# BreakoutBoard.net
KiCad netlist of a schematic drawn in EAGLE
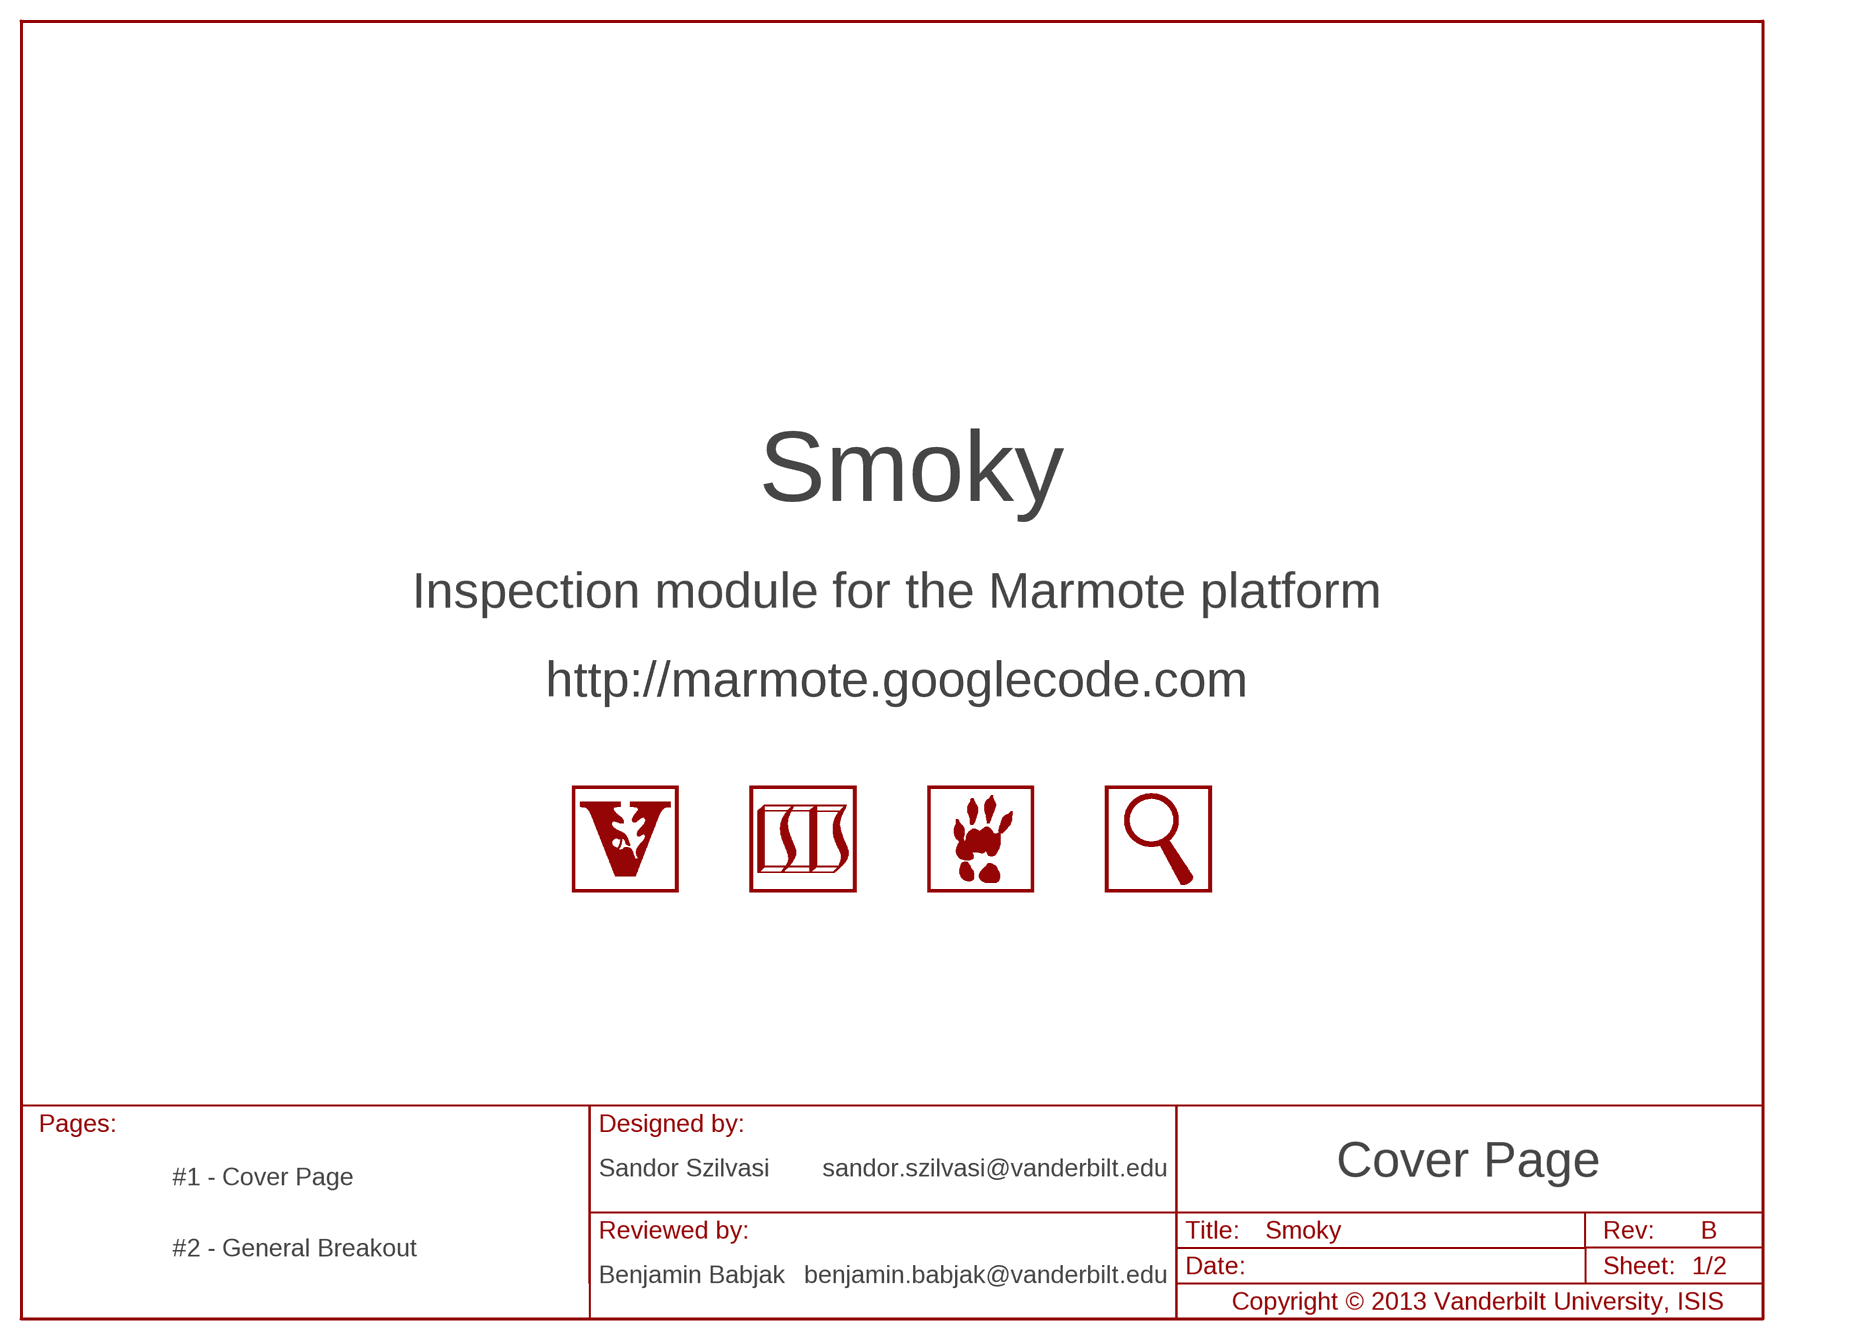
[diagram p0: schematic, sheet 1]
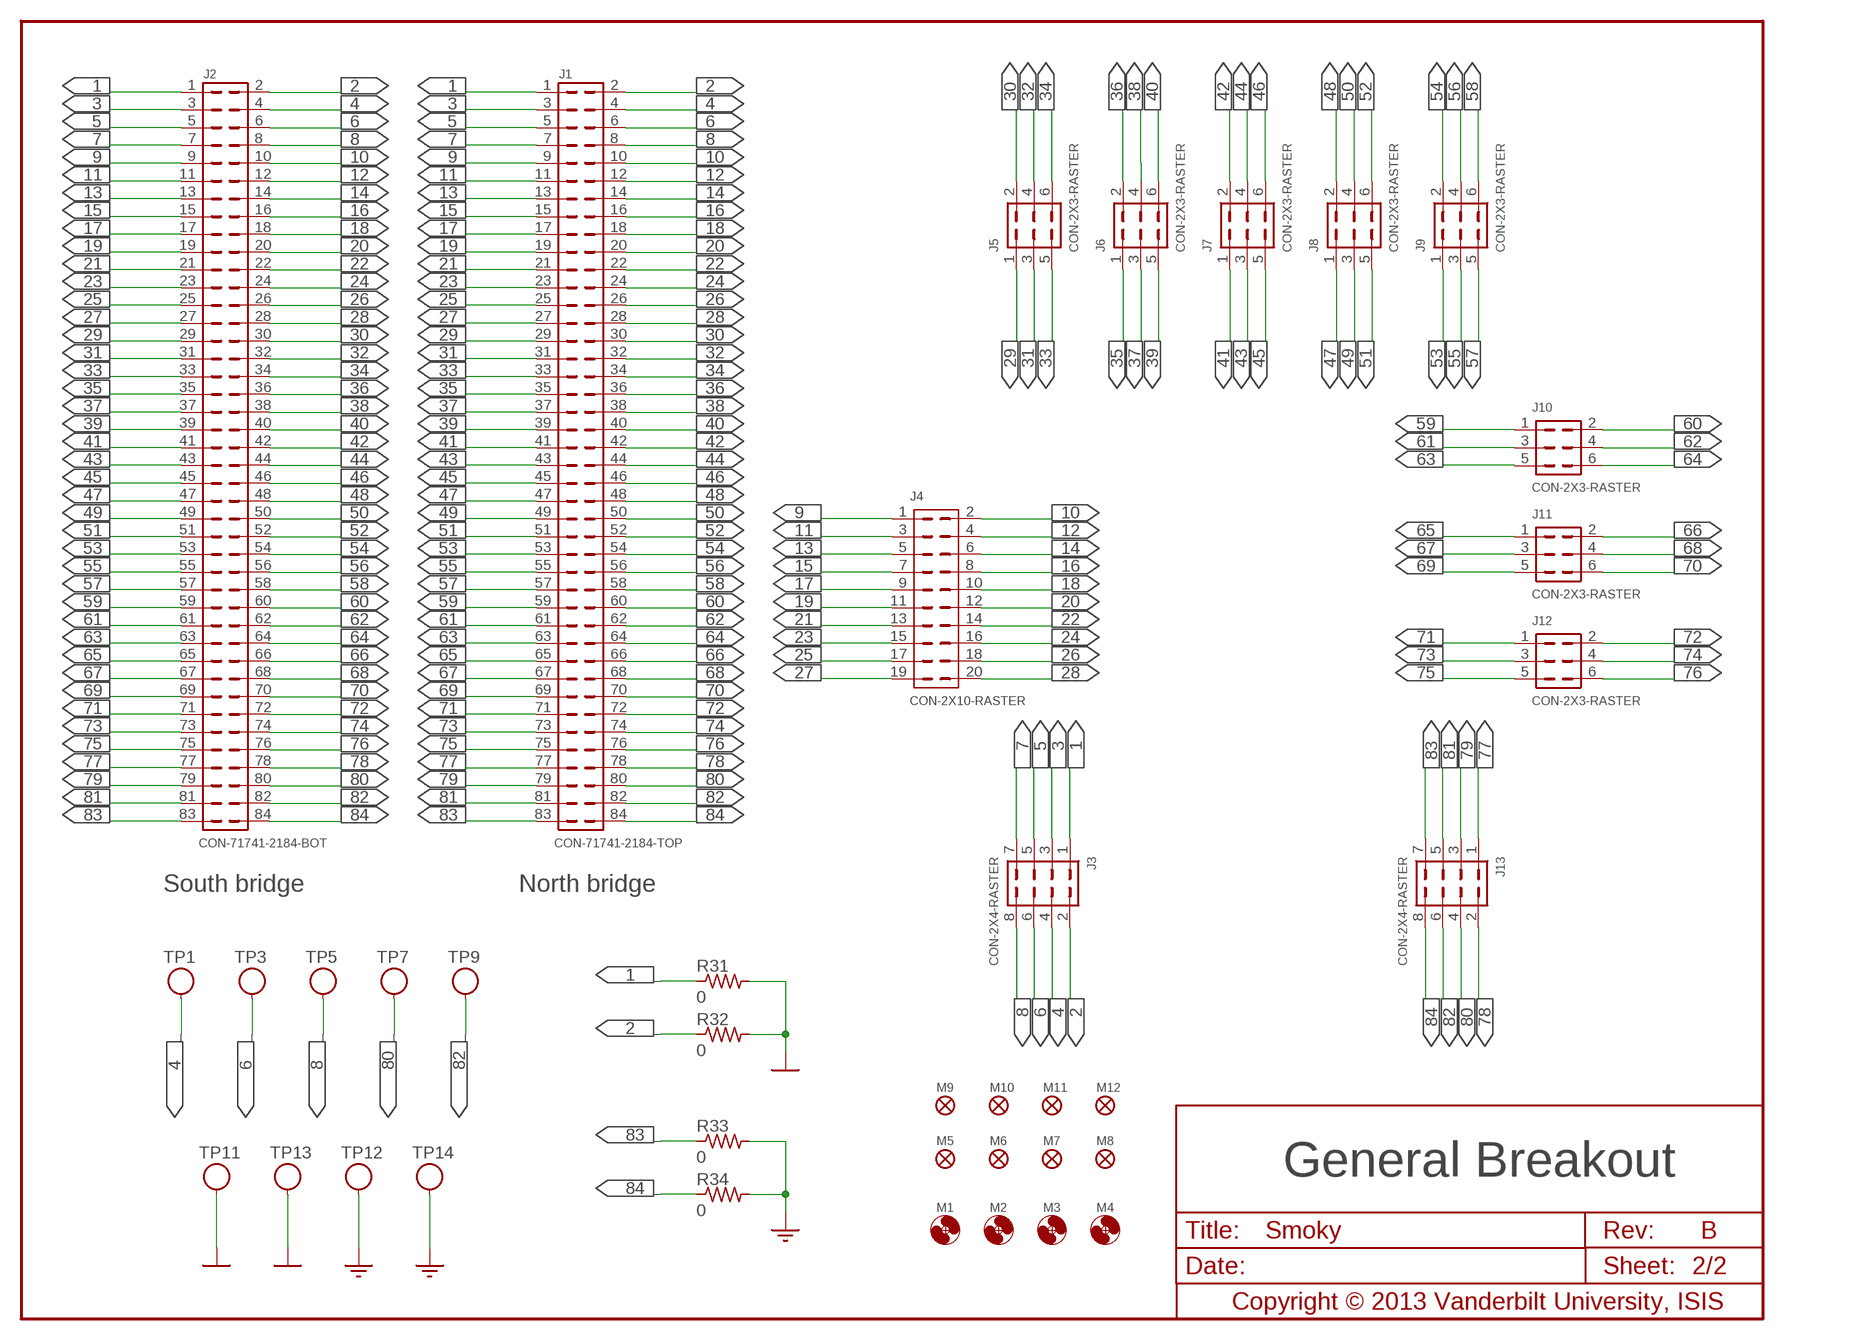
[diagram p1: schematic, sheet 2]

(export (version "E")
  (design (tool "Eeschema 10.0.6"))
  (components
    (comp (ref "LOGO1")
      (value "LOGO-MAGNIFYING-GLASS-600MIL-10MM-SS")
      (footprint "eagle-import:LOGO-MAGNIFYING-GLASS-10MM-SILKSCREEN")
      (libsource (lib "eagle-import") (part "LOGO-MAGNIFYING-GLASS-600MIL-10MM-SS"))
    )
    (comp (ref "LOGO5")
      (value "LOGO-VANDERBILT-600MIL-10MM-SS")
      (footprint "eagle-import:LOGO-VANDERBILT-10MM-SILKSCREEN")
      (libsource (lib "eagle-import") (part "LOGO-VANDERBILT-600MIL-10MM-SS"))
    )
    (comp (ref "LOGO6")
      (value "LOGO-ISIS-600MIL-10MM-SS")
      (footprint "eagle-import:LOGO-ISIS-10MM-SILKSCREEN")
      (libsource (lib "eagle-import") (part "LOGO-ISIS-600MIL-10MM-SS"))
    )
    (comp (ref "LOGO7")
      (value "LOGO-MARMOTE-600MIL-10MM-SS")
      (footprint "eagle-import:LOGO-MARMOTE-10MM-SILKSCREEN")
      (libsource (lib "eagle-import") (part "LOGO-MARMOTE-600MIL-10MM-SS"))
    )
    (comp (ref "J1")
      (value "CON-71741-2184-TOP")
      (footprint "eagle-import:71741-0002")
      (fields (field (name "MF") "Molex") (field (name "MPN") "71741-0002"))
      (libsource (lib "eagle-import") (part "CON-7174184-TOP-21"))
    )
    (comp (ref "J2")
      (value "CON-71741-2184-BOT")
      (footprint "eagle-import:71742-3003-BOT")
      (fields (field (name "MF") "Molex") (field (name "MPN") "71742-3003"))
      (libsource (lib "eagle-import") (part "CON-7174184-BOT-21"))
    )
    (comp (ref "J3")
      (value "CON-2X4-RASTER")
      (footprint "eagle-import:2X8")
      (libsource (lib "eagle-import") (part "CON-2X4-RASTER"))
    )
    (comp (ref "J4")
      (value "CON-2X10-RASTER")
      (footprint "eagle-import:2X20")
      (libsource (lib "eagle-import") (part "CON-2X10-RASTER"))
    )
    (comp (ref "J5")
      (value "CON-2X3-RASTER")
      (footprint "eagle-import:2X6")
      (libsource (lib "eagle-import") (part "CON-2X3-RASTER"))
    )
    (comp (ref "J6")
      (value "CON-2X3-RASTER")
      (footprint "eagle-import:2X6")
      (libsource (lib "eagle-import") (part "CON-2X3-RASTER"))
    )
    (comp (ref "J7")
      (value "CON-2X3-RASTER")
      (footprint "eagle-import:2X6")
      (libsource (lib "eagle-import") (part "CON-2X3-RASTER"))
    )
    (comp (ref "J8")
      (value "CON-2X3-RASTER")
      (footprint "eagle-import:2X6")
      (libsource (lib "eagle-import") (part "CON-2X3-RASTER"))
    )
    (comp (ref "J9")
      (value "CON-2X3-RASTER")
      (footprint "eagle-import:2X6")
      (libsource (lib "eagle-import") (part "CON-2X3-RASTER"))
    )
    (comp (ref "J10")
      (value "CON-2X3-RASTER")
      (footprint "eagle-import:2X6")
      (libsource (lib "eagle-import") (part "CON-2X3-RASTER"))
    )
    (comp (ref "J11")
      (value "CON-2X3-RASTER")
      (footprint "eagle-import:2X6")
      (libsource (lib "eagle-import") (part "CON-2X3-RASTER"))
    )
    (comp (ref "J12")
      (value "CON-2X3-RASTER")
      (footprint "eagle-import:2X6")
      (libsource (lib "eagle-import") (part "CON-2X3-RASTER"))
    )
    (comp (ref "J13")
      (value "CON-2X4-RASTER")
      (footprint "eagle-import:2X8")
      (libsource (lib "eagle-import") (part "CON-2X4-RASTER"))
    )
    (comp (ref "M1")
      (value "MOUNT-HOLE3.3")
      (footprint "eagle-import:3,3")
      (libsource (lib "eagle-import") (part "MOUNT-HOLE3.3"))
    )
    (comp (ref "M2")
      (value "MOUNT-HOLE3.3")
      (footprint "eagle-import:3,3")
      (libsource (lib "eagle-import") (part "MOUNT-HOLE3.3"))
    )
    (comp (ref "M3")
      (value "MOUNT-HOLE3.3")
      (footprint "eagle-import:3,3")
      (libsource (lib "eagle-import") (part "MOUNT-HOLE3.3"))
    )
    (comp (ref "M4")
      (value "MOUNT-HOLE3.3")
      (footprint "eagle-import:3,3")
      (libsource (lib "eagle-import") (part "MOUNT-HOLE3.3"))
    )
    (comp (ref "M5")
      (value "FIDUCIAL1X2")
      (footprint "eagle-import:FIDUCIAL-1X2")
      (libsource (lib "eagle-import") (part "FIDUCIAL1X2"))
    )
    (comp (ref "M6")
      (value "FIDUCIAL1X2")
      (footprint "eagle-import:FIDUCIAL-1X2")
      (libsource (lib "eagle-import") (part "FIDUCIAL1X2"))
    )
    (comp (ref "M7")
      (value "FIDUCIAL1X2")
      (footprint "eagle-import:FIDUCIAL-1X2")
      (libsource (lib "eagle-import") (part "FIDUCIAL1X2"))
    )
    (comp (ref "M8")
      (value "FIDUCIAL1X2")
      (footprint "eagle-import:FIDUCIAL-1X2")
      (libsource (lib "eagle-import") (part "FIDUCIAL1X2"))
    )
    (comp (ref "M9")
      (value "FIDUCIAL1X2")
      (footprint "eagle-import:FIDUCIAL-1X2")
      (libsource (lib "eagle-import") (part "FIDUCIAL1X2"))
    )
    (comp (ref "M10")
      (value "FIDUCIAL1X2")
      (footprint "eagle-import:FIDUCIAL-1X2")
      (libsource (lib "eagle-import") (part "FIDUCIAL1X2"))
    )
    (comp (ref "M11")
      (value "FIDUCIAL1X2")
      (footprint "eagle-import:FIDUCIAL-1X2")
      (libsource (lib "eagle-import") (part "FIDUCIAL1X2"))
    )
    (comp (ref "M12")
      (value "FIDUCIAL1X2")
      (footprint "eagle-import:FIDUCIAL-1X2")
      (libsource (lib "eagle-import") (part "FIDUCIAL1X2"))
    )
    (comp (ref "R31")
      (value "0")
      (footprint "eagle-import:R0805")
      (libsource (lib "eagle-import") (part "R0805"))
    )
    (comp (ref "R32")
      (value "0")
      (footprint "eagle-import:R0805")
      (libsource (lib "eagle-import") (part "R0805"))
    )
    (comp (ref "R33")
      (value "0")
      (footprint "eagle-import:R0805")
      (libsource (lib "eagle-import") (part "R0805"))
    )
    (comp (ref "R34")
      (value "0")
      (footprint "eagle-import:R0805")
      (libsource (lib "eagle-import") (part "R0805"))
    )
    (comp (ref "TP1")
      (value "TESTPOINT-BLUE")
      (footprint "eagle-import:TESTPOINT")
      (fields (field (name "MF") "Keystone") (field (name "MPN") "5122"))
      (libsource (lib "eagle-import") (part "TESTPOINT-BLUE"))
    )
    (comp (ref "TP3")
      (value "TESTPOINT-BLUE")
      (footprint "eagle-import:TESTPOINT")
      (fields (field (name "MF") "Keystone") (field (name "MPN") "5122"))
      (libsource (lib "eagle-import") (part "TESTPOINT-BLUE"))
    )
    (comp (ref "TP5")
      (value "TESTPOINT-BLUE")
      (footprint "eagle-import:TESTPOINT")
      (fields (field (name "MF") "Keystone") (field (name "MPN") "5122"))
      (libsource (lib "eagle-import") (part "TESTPOINT-BLUE"))
    )
    (comp (ref "TP7")
      (value "TESTPOINT-GREEN")
      (footprint "eagle-import:TESTPOINT")
      (fields (field (name "MF") "Keystone") (field (name "MPN") "5121"))
      (libsource (lib "eagle-import") (part "TESTPOINT-GREEN"))
    )
    (comp (ref "TP9")
      (value "TESTPOINT-GREEN")
      (footprint "eagle-import:TESTPOINT")
      (fields (field (name "MF") "Keystone") (field (name "MPN") "5121"))
      (libsource (lib "eagle-import") (part "TESTPOINT-GREEN"))
    )
    (comp (ref "TP11")
      (value "TESTPOINT-YELLOW")
      (footprint "eagle-import:TESTPOINT")
      (fields (field (name "MF") "Keystone") (field (name "MPN") "5009"))
      (libsource (lib "eagle-import") (part "TESTPOINT-YELLOW"))
    )
    (comp (ref "TP12")
      (value "TESTPOINT-YELLOW")
      (footprint "eagle-import:TESTPOINT")
      (fields (field (name "MF") "Keystone") (field (name "MPN") "5009"))
      (libsource (lib "eagle-import") (part "TESTPOINT-YELLOW"))
    )
    (comp (ref "TP13")
      (value "TESTPOINT-YELLOW")
      (footprint "eagle-import:TESTPOINT")
      (fields (field (name "MF") "Keystone") (field (name "MPN") "5009"))
      (libsource (lib "eagle-import") (part "TESTPOINT-YELLOW"))
    )
    (comp (ref "TP14")
      (value "TESTPOINT-YELLOW")
      (footprint "eagle-import:TESTPOINT")
      (fields (field (name "MF") "Keystone") (field (name "MPN") "5009"))
      (libsource (lib "eagle-import") (part "TESTPOINT-YELLOW"))
    )
  )
  (nets
    (net (code "1") (name "1") (class "Default")
      (node (ref "J1") (pin "1") (pinfunction "1_1") (pintype "passive"))
      (node (ref "J2") (pin "1") (pinfunction "1_1") (pintype "passive"))
      (node (ref "J3") (pin "1") (pinfunction "1_1") (pintype "passive"))
      (node (ref "R31") (pin "1") (pinfunction "1_1") (pintype "passive"))
    )
    (net (code "2") (name "2") (class "Default")
      (node (ref "J1") (pin "2") (pinfunction "2_2") (pintype "passive"))
      (node (ref "J2") (pin "2") (pinfunction "2_2") (pintype "passive"))
      (node (ref "J3") (pin "2") (pinfunction "2_2") (pintype "passive"))
      (node (ref "R32") (pin "1") (pinfunction "1_1") (pintype "passive"))
    )
    (net (code "3") (name "3") (class "Default")
      (node (ref "J1") (pin "3") (pinfunction "3_3") (pintype "passive"))
      (node (ref "J2") (pin "3") (pinfunction "3_3") (pintype "passive"))
      (node (ref "J3") (pin "3") (pinfunction "3_3") (pintype "passive"))
    )
    (net (code "4") (name "4") (class "Default")
      (node (ref "J1") (pin "4") (pinfunction "4_4") (pintype "passive"))
      (node (ref "J2") (pin "4") (pinfunction "4_4") (pintype "passive"))
      (node (ref "J3") (pin "4") (pinfunction "4_4") (pintype "passive"))
      (node (ref "TP1") (pin "1") (pinfunction "1_1") (pintype "power_in"))
    )
    (net (code "5") (name "5") (class "Default")
      (node (ref "J1") (pin "5") (pinfunction "5_5") (pintype "passive"))
      (node (ref "J2") (pin "5") (pinfunction "5_5") (pintype "passive"))
      (node (ref "J3") (pin "5") (pinfunction "5_5") (pintype "passive"))
    )
    (net (code "6") (name "6") (class "Default")
      (node (ref "J1") (pin "6") (pinfunction "6_6") (pintype "passive"))
      (node (ref "J2") (pin "6") (pinfunction "6_6") (pintype "passive"))
      (node (ref "J3") (pin "6") (pinfunction "6_6") (pintype "passive"))
      (node (ref "TP3") (pin "1") (pinfunction "1_1") (pintype "power_in"))
    )
    (net (code "7") (name "7") (class "Default")
      (node (ref "J1") (pin "7") (pinfunction "7_7") (pintype "passive"))
      (node (ref "J2") (pin "7") (pinfunction "7_7") (pintype "passive"))
      (node (ref "J3") (pin "7") (pinfunction "7_7") (pintype "passive"))
    )
    (net (code "8") (name "8") (class "Default")
      (node (ref "J1") (pin "8") (pinfunction "8_8") (pintype "passive"))
      (node (ref "J2") (pin "8") (pinfunction "8_8") (pintype "passive"))
      (node (ref "J3") (pin "8") (pinfunction "8_8") (pintype "passive"))
      (node (ref "TP5") (pin "1") (pinfunction "1_1") (pintype "power_in"))
    )
    (net (code "9") (name "9") (class "Default")
      (node (ref "J1") (pin "9") (pinfunction "9_9") (pintype "passive"))
      (node (ref "J2") (pin "9") (pinfunction "9_9") (pintype "passive"))
      (node (ref "J4") (pin "1") (pinfunction "1_1") (pintype "passive"))
    )
    (net (code "10") (name "10") (class "Default")
      (node (ref "J1") (pin "10") (pinfunction "10_10") (pintype "passive"))
      (node (ref "J2") (pin "10") (pinfunction "10_10") (pintype "passive"))
      (node (ref "J4") (pin "2") (pinfunction "2_2") (pintype "passive"))
    )
    (net (code "11") (name "11") (class "Default")
      (node (ref "J1") (pin "11") (pinfunction "11_11") (pintype "passive"))
      (node (ref "J2") (pin "11") (pinfunction "11_11") (pintype "passive"))
      (node (ref "J4") (pin "3") (pinfunction "3_3") (pintype "passive"))
    )
    (net (code "12") (name "12") (class "Default")
      (node (ref "J1") (pin "12") (pinfunction "12_12") (pintype "passive"))
      (node (ref "J2") (pin "12") (pinfunction "12_12") (pintype "passive"))
      (node (ref "J4") (pin "4") (pinfunction "4_4") (pintype "passive"))
    )
    (net (code "13") (name "13") (class "Default")
      (node (ref "J1") (pin "13") (pinfunction "13_13") (pintype "passive"))
      (node (ref "J2") (pin "13") (pinfunction "13_13") (pintype "passive"))
      (node (ref "J4") (pin "5") (pinfunction "5_5") (pintype "passive"))
    )
    (net (code "14") (name "14") (class "Default")
      (node (ref "J1") (pin "14") (pinfunction "14_14") (pintype "passive"))
      (node (ref "J2") (pin "14") (pinfunction "14_14") (pintype "passive"))
      (node (ref "J4") (pin "6") (pinfunction "6_6") (pintype "passive"))
    )
    (net (code "15") (name "15") (class "Default")
      (node (ref "J1") (pin "15") (pinfunction "15_15") (pintype "passive"))
      (node (ref "J2") (pin "15") (pinfunction "15_15") (pintype "passive"))
      (node (ref "J4") (pin "7") (pinfunction "7_7") (pintype "passive"))
    )
    (net (code "16") (name "16") (class "Default")
      (node (ref "J1") (pin "16") (pinfunction "16_16") (pintype "passive"))
      (node (ref "J2") (pin "16") (pinfunction "16_16") (pintype "passive"))
      (node (ref "J4") (pin "8") (pinfunction "8_8") (pintype "passive"))
    )
    (net (code "17") (name "17") (class "Default")
      (node (ref "J1") (pin "17") (pinfunction "17_17") (pintype "passive"))
      (node (ref "J2") (pin "17") (pinfunction "17_17") (pintype "passive"))
      (node (ref "J4") (pin "9") (pinfunction "9_9") (pintype "passive"))
    )
    (net (code "18") (name "18") (class "Default")
      (node (ref "J1") (pin "18") (pinfunction "18_18") (pintype "passive"))
      (node (ref "J2") (pin "18") (pinfunction "18_18") (pintype "passive"))
      (node (ref "J4") (pin "10") (pinfunction "10_10") (pintype "passive"))
    )
    (net (code "19") (name "19") (class "Default")
      (node (ref "J1") (pin "19") (pinfunction "19_19") (pintype "passive"))
      (node (ref "J2") (pin "19") (pinfunction "19_19") (pintype "passive"))
      (node (ref "J4") (pin "11") (pinfunction "11_11") (pintype "passive"))
    )
    (net (code "20") (name "20") (class "Default")
      (node (ref "J1") (pin "20") (pinfunction "20_20") (pintype "passive"))
      (node (ref "J2") (pin "20") (pinfunction "20_20") (pintype "passive"))
      (node (ref "J4") (pin "12") (pinfunction "12_12") (pintype "passive"))
    )
    (net (code "21") (name "21") (class "Default")
      (node (ref "J1") (pin "21") (pinfunction "21_21") (pintype "passive"))
      (node (ref "J2") (pin "21") (pinfunction "21_21") (pintype "passive"))
      (node (ref "J4") (pin "13") (pinfunction "13_13") (pintype "passive"))
    )
    (net (code "22") (name "22") (class "Default")
      (node (ref "J1") (pin "22") (pinfunction "22_22") (pintype "passive"))
      (node (ref "J2") (pin "22") (pinfunction "22_22") (pintype "passive"))
      (node (ref "J4") (pin "14") (pinfunction "14_14") (pintype "passive"))
    )
    (net (code "23") (name "23") (class "Default")
      (node (ref "J1") (pin "23") (pinfunction "23_23") (pintype "passive"))
      (node (ref "J2") (pin "23") (pinfunction "23_23") (pintype "passive"))
      (node (ref "J4") (pin "15") (pinfunction "15_15") (pintype "passive"))
    )
    (net (code "24") (name "24") (class "Default")
      (node (ref "J1") (pin "24") (pinfunction "24_24") (pintype "passive"))
      (node (ref "J2") (pin "24") (pinfunction "24_24") (pintype "passive"))
      (node (ref "J4") (pin "16") (pinfunction "16_16") (pintype "passive"))
    )
    (net (code "25") (name "25") (class "Default")
      (node (ref "J1") (pin "25") (pinfunction "25_25") (pintype "passive"))
      (node (ref "J2") (pin "25") (pinfunction "25_25") (pintype "passive"))
      (node (ref "J4") (pin "17") (pinfunction "17_17") (pintype "passive"))
    )
    (net (code "26") (name "26") (class "Default")
      (node (ref "J1") (pin "26") (pinfunction "26_26") (pintype "passive"))
      (node (ref "J2") (pin "26") (pinfunction "26_26") (pintype "passive"))
      (node (ref "J4") (pin "18") (pinfunction "18_18") (pintype "passive"))
    )
    (net (code "27") (name "27") (class "Default")
      (node (ref "J1") (pin "27") (pinfunction "27_27") (pintype "passive"))
      (node (ref "J2") (pin "27") (pinfunction "27_27") (pintype "passive"))
      (node (ref "J4") (pin "19") (pinfunction "19_19") (pintype "passive"))
    )
    (net (code "28") (name "28") (class "Default")
      (node (ref "J1") (pin "28") (pinfunction "28_28") (pintype "passive"))
      (node (ref "J2") (pin "28") (pinfunction "28_28") (pintype "passive"))
      (node (ref "J4") (pin "20") (pinfunction "20_20") (pintype "passive"))
    )
    (net (code "29") (name "29") (class "Default")
      (node (ref "J1") (pin "29") (pinfunction "29_29") (pintype "passive"))
      (node (ref "J2") (pin "29") (pinfunction "29_29") (pintype "passive"))
      (node (ref "J5") (pin "1") (pinfunction "1_1") (pintype "passive"))
    )
    (net (code "30") (name "30") (class "Default")
      (node (ref "J1") (pin "30") (pinfunction "30_30") (pintype "passive"))
      (node (ref "J2") (pin "30") (pinfunction "30_30") (pintype "passive"))
      (node (ref "J5") (pin "2") (pinfunction "2_2") (pintype "passive"))
    )
    (net (code "31") (name "31") (class "Default")
      (node (ref "J1") (pin "31") (pinfunction "31_31") (pintype "passive"))
      (node (ref "J2") (pin "31") (pinfunction "31_31") (pintype "passive"))
      (node (ref "J5") (pin "3") (pinfunction "3_3") (pintype "passive"))
    )
    (net (code "32") (name "32") (class "Default")
      (node (ref "J1") (pin "32") (pinfunction "32_32") (pintype "passive"))
      (node (ref "J2") (pin "32") (pinfunction "32_32") (pintype "passive"))
      (node (ref "J5") (pin "4") (pinfunction "4_4") (pintype "passive"))
    )
    (net (code "33") (name "33") (class "Default")
      (node (ref "J1") (pin "33") (pinfunction "33_33") (pintype "passive"))
      (node (ref "J2") (pin "33") (pinfunction "33_33") (pintype "passive"))
      (node (ref "J5") (pin "5") (pinfunction "5_5") (pintype "passive"))
    )
    (net (code "34") (name "34") (class "Default")
      (node (ref "J1") (pin "34") (pinfunction "34_34") (pintype "passive"))
      (node (ref "J2") (pin "34") (pinfunction "34_34") (pintype "passive"))
      (node (ref "J5") (pin "6") (pinfunction "6_6") (pintype "passive"))
    )
    (net (code "35") (name "35") (class "Default")
      (node (ref "J1") (pin "35") (pinfunction "35_35") (pintype "passive"))
      (node (ref "J2") (pin "35") (pinfunction "35_35") (pintype "passive"))
      (node (ref "J6") (pin "1") (pinfunction "1_1") (pintype "passive"))
    )
    (net (code "36") (name "36") (class "Default")
      (node (ref "J1") (pin "36") (pinfunction "36_36") (pintype "passive"))
      (node (ref "J2") (pin "36") (pinfunction "36_36") (pintype "passive"))
      (node (ref "J6") (pin "2") (pinfunction "2_2") (pintype "passive"))
    )
    (net (code "37") (name "37") (class "Default")
      (node (ref "J1") (pin "37") (pinfunction "37_37") (pintype "passive"))
      (node (ref "J2") (pin "37") (pinfunction "37_37") (pintype "passive"))
      (node (ref "J6") (pin "3") (pinfunction "3_3") (pintype "passive"))
    )
    (net (code "38") (name "38") (class "Default")
      (node (ref "J1") (pin "38") (pinfunction "38_38") (pintype "passive"))
      (node (ref "J2") (pin "38") (pinfunction "38_38") (pintype "passive"))
      (node (ref "J6") (pin "4") (pinfunction "4_4") (pintype "passive"))
    )
    (net (code "39") (name "39") (class "Default")
      (node (ref "J1") (pin "39") (pinfunction "39_39") (pintype "passive"))
      (node (ref "J2") (pin "39") (pinfunction "39_39") (pintype "passive"))
      (node (ref "J6") (pin "5") (pinfunction "5_5") (pintype "passive"))
    )
    (net (code "40") (name "40") (class "Default")
      (node (ref "J1") (pin "40") (pinfunction "40_40") (pintype "passive"))
      (node (ref "J2") (pin "40") (pinfunction "40_40") (pintype "passive"))
      (node (ref "J6") (pin "6") (pinfunction "6_6") (pintype "passive"))
    )
    (net (code "41") (name "41") (class "Default")
      (node (ref "J1") (pin "41") (pinfunction "41_41") (pintype "passive"))
      (node (ref "J2") (pin "41") (pinfunction "41_41") (pintype "passive"))
      (node (ref "J7") (pin "1") (pinfunction "1_1") (pintype "passive"))
    )
    (net (code "42") (name "42") (class "Default")
      (node (ref "J1") (pin "42") (pinfunction "42_42") (pintype "passive"))
      (node (ref "J2") (pin "42") (pinfunction "42_42") (pintype "passive"))
      (node (ref "J7") (pin "2") (pinfunction "2_2") (pintype "passive"))
    )
    (net (code "43") (name "43") (class "Default")
      (node (ref "J1") (pin "43") (pinfunction "43_43") (pintype "passive"))
      (node (ref "J2") (pin "43") (pinfunction "43_43") (pintype "passive"))
      (node (ref "J7") (pin "3") (pinfunction "3_3") (pintype "passive"))
    )
    (net (code "44") (name "44") (class "Default")
      (node (ref "J1") (pin "44") (pinfunction "44_44") (pintype "passive"))
      (node (ref "J2") (pin "44") (pinfunction "44_44") (pintype "passive"))
      (node (ref "J7") (pin "4") (pinfunction "4_4") (pintype "passive"))
    )
    (net (code "45") (name "45") (class "Default")
      (node (ref "J1") (pin "45") (pinfunction "45_45") (pintype "passive"))
      (node (ref "J2") (pin "45") (pinfunction "45_45") (pintype "passive"))
      (node (ref "J7") (pin "5") (pinfunction "5_5") (pintype "passive"))
    )
    (net (code "46") (name "46") (class "Default")
      (node (ref "J1") (pin "46") (pinfunction "46_46") (pintype "passive"))
      (node (ref "J2") (pin "46") (pinfunction "46_46") (pintype "passive"))
      (node (ref "J7") (pin "6") (pinfunction "6_6") (pintype "passive"))
    )
    (net (code "47") (name "47") (class "Default")
      (node (ref "J1") (pin "47") (pinfunction "47_47") (pintype "passive"))
      (node (ref "J2") (pin "47") (pinfunction "47_47") (pintype "passive"))
      (node (ref "J8") (pin "1") (pinfunction "1_1") (pintype "passive"))
    )
    (net (code "48") (name "48") (class "Default")
      (node (ref "J1") (pin "48") (pinfunction "48_48") (pintype "passive"))
      (node (ref "J2") (pin "48") (pinfunction "48_48") (pintype "passive"))
      (node (ref "J8") (pin "2") (pinfunction "2_2") (pintype "passive"))
    )
    (net (code "49") (name "49") (class "Default")
      (node (ref "J1") (pin "49") (pinfunction "49_49") (pintype "passive"))
      (node (ref "J2") (pin "49") (pinfunction "49_49") (pintype "passive"))
      (node (ref "J8") (pin "3") (pinfunction "3_3") (pintype "passive"))
    )
    (net (code "50") (name "50") (class "Default")
      (node (ref "J1") (pin "50") (pinfunction "50_50") (pintype "passive"))
      (node (ref "J2") (pin "50") (pinfunction "50_50") (pintype "passive"))
      (node (ref "J8") (pin "4") (pinfunction "4_4") (pintype "passive"))
    )
    (net (code "51") (name "51") (class "Default")
      (node (ref "J1") (pin "51") (pinfunction "51_51") (pintype "passive"))
      (node (ref "J2") (pin "51") (pinfunction "51_51") (pintype "passive"))
      (node (ref "J8") (pin "5") (pinfunction "5_5") (pintype "passive"))
    )
    (net (code "52") (name "52") (class "Default")
      (node (ref "J1") (pin "52") (pinfunction "52_52") (pintype "passive"))
      (node (ref "J2") (pin "52") (pinfunction "52_52") (pintype "passive"))
      (node (ref "J8") (pin "6") (pinfunction "6_6") (pintype "passive"))
    )
    (net (code "53") (name "53") (class "Default")
      (node (ref "J1") (pin "53") (pinfunction "53_53") (pintype "passive"))
      (node (ref "J2") (pin "53") (pinfunction "53_53") (pintype "passive"))
      (node (ref "J9") (pin "1") (pinfunction "1_1") (pintype "passive"))
    )
    (net (code "54") (name "54") (class "Default")
      (node (ref "J1") (pin "54") (pinfunction "54_54") (pintype "passive"))
      (node (ref "J2") (pin "54") (pinfunction "54_54") (pintype "passive"))
      (node (ref "J9") (pin "2") (pinfunction "2_2") (pintype "passive"))
    )
    (net (code "55") (name "55") (class "Default")
      (node (ref "J1") (pin "55") (pinfunction "55_55") (pintype "passive"))
      (node (ref "J2") (pin "55") (pinfunction "55_55") (pintype "passive"))
      (node (ref "J9") (pin "3") (pinfunction "3_3") (pintype "passive"))
    )
    (net (code "56") (name "56") (class "Default")
      (node (ref "J1") (pin "56") (pinfunction "56_56") (pintype "passive"))
      (node (ref "J2") (pin "56") (pinfunction "56_56") (pintype "passive"))
      (node (ref "J9") (pin "4") (pinfunction "4_4") (pintype "passive"))
    )
    (net (code "57") (name "57") (class "Default")
      (node (ref "J1") (pin "57") (pinfunction "57_57") (pintype "passive"))
      (node (ref "J2") (pin "57") (pinfunction "57_57") (pintype "passive"))
      (node (ref "J9") (pin "5") (pinfunction "5_5") (pintype "passive"))
    )
    (net (code "58") (name "58") (class "Default")
      (node (ref "J1") (pin "58") (pinfunction "58_58") (pintype "passive"))
      (node (ref "J2") (pin "58") (pinfunction "58_58") (pintype "passive"))
      (node (ref "J9") (pin "6") (pinfunction "6_6") (pintype "passive"))
    )
    (net (code "59") (name "59") (class "Default")
      (node (ref "J1") (pin "59") (pinfunction "59_59") (pintype "passive"))
      (node (ref "J10") (pin "1") (pinfunction "1_1") (pintype "passive"))
      (node (ref "J2") (pin "59") (pinfunction "59_59") (pintype "passive"))
    )
    (net (code "60") (name "60") (class "Default")
      (node (ref "J1") (pin "60") (pinfunction "60_60") (pintype "passive"))
      (node (ref "J10") (pin "2") (pinfunction "2_2") (pintype "passive"))
      (node (ref "J2") (pin "60") (pinfunction "60_60") (pintype "passive"))
    )
    (net (code "61") (name "61") (class "Default")
      (node (ref "J1") (pin "61") (pinfunction "61_61") (pintype "passive"))
      (node (ref "J10") (pin "3") (pinfunction "3_3") (pintype "passive"))
      (node (ref "J2") (pin "61") (pinfunction "61_61") (pintype "passive"))
    )
    (net (code "62") (name "62") (class "Default")
      (node (ref "J1") (pin "62") (pinfunction "62_62") (pintype "passive"))
      (node (ref "J10") (pin "4") (pinfunction "4_4") (pintype "passive"))
      (node (ref "J2") (pin "62") (pinfunction "62_62") (pintype "passive"))
    )
    (net (code "63") (name "63") (class "Default")
      (node (ref "J1") (pin "63") (pinfunction "63_63") (pintype "passive"))
      (node (ref "J10") (pin "5") (pinfunction "5_5") (pintype "passive"))
      (node (ref "J2") (pin "63") (pinfunction "63_63") (pintype "passive"))
    )
    (net (code "64") (name "64") (class "Default")
      (node (ref "J1") (pin "64") (pinfunction "64_64") (pintype "passive"))
      (node (ref "J10") (pin "6") (pinfunction "6_6") (pintype "passive"))
      (node (ref "J2") (pin "64") (pinfunction "64_64") (pintype "passive"))
    )
    (net (code "65") (name "65") (class "Default")
      (node (ref "J1") (pin "65") (pinfunction "65_65") (pintype "passive"))
      (node (ref "J11") (pin "1") (pinfunction "1_1") (pintype "passive"))
      (node (ref "J2") (pin "65") (pinfunction "65_65") (pintype "passive"))
    )
    (net (code "66") (name "66") (class "Default")
      (node (ref "J1") (pin "66") (pinfunction "66_66") (pintype "passive"))
      (node (ref "J11") (pin "2") (pinfunction "2_2") (pintype "passive"))
      (node (ref "J2") (pin "66") (pinfunction "66_66") (pintype "passive"))
    )
    (net (code "67") (name "67") (class "Default")
      (node (ref "J1") (pin "67") (pinfunction "67_67") (pintype "passive"))
      (node (ref "J11") (pin "3") (pinfunction "3_3") (pintype "passive"))
      (node (ref "J2") (pin "67") (pinfunction "67_67") (pintype "passive"))
    )
    (net (code "68") (name "68") (class "Default")
      (node (ref "J1") (pin "68") (pinfunction "68_68") (pintype "passive"))
      (node (ref "J11") (pin "4") (pinfunction "4_4") (pintype "passive"))
      (node (ref "J2") (pin "68") (pinfunction "68_68") (pintype "passive"))
    )
    (net (code "69") (name "69") (class "Default")
      (node (ref "J1") (pin "69") (pinfunction "69_69") (pintype "passive"))
      (node (ref "J11") (pin "5") (pinfunction "5_5") (pintype "passive"))
      (node (ref "J2") (pin "69") (pinfunction "69_69") (pintype "passive"))
    )
    (net (code "70") (name "70") (class "Default")
      (node (ref "J1") (pin "70") (pinfunction "70_70") (pintype "passive"))
      (node (ref "J11") (pin "6") (pinfunction "6_6") (pintype "passive"))
      (node (ref "J2") (pin "70") (pinfunction "70_70") (pintype "passive"))
    )
    (net (code "71") (name "71") (class "Default")
      (node (ref "J1") (pin "71") (pinfunction "71_71") (pintype "passive"))
      (node (ref "J12") (pin "1") (pinfunction "1_1") (pintype "passive"))
      (node (ref "J2") (pin "71") (pinfunction "71_71") (pintype "passive"))
    )
    (net (code "72") (name "72") (class "Default")
      (node (ref "J1") (pin "72") (pinfunction "72_72") (pintype "passive"))
      (node (ref "J12") (pin "2") (pinfunction "2_2") (pintype "passive"))
      (node (ref "J2") (pin "72") (pinfunction "72_72") (pintype "passive"))
    )
    (net (code "73") (name "73") (class "Default")
      (node (ref "J1") (pin "73") (pinfunction "73_73") (pintype "passive"))
      (node (ref "J12") (pin "3") (pinfunction "3_3") (pintype "passive"))
      (node (ref "J2") (pin "73") (pinfunction "73_73") (pintype "passive"))
    )
    (net (code "74") (name "74") (class "Default")
      (node (ref "J1") (pin "74") (pinfunction "74_74") (pintype "passive"))
      (node (ref "J12") (pin "4") (pinfunction "4_4") (pintype "passive"))
      (node (ref "J2") (pin "74") (pinfunction "74_74") (pintype "passive"))
    )
    (net (code "75") (name "75") (class "Default")
      (node (ref "J1") (pin "75") (pinfunction "75_75") (pintype "passive"))
      (node (ref "J12") (pin "5") (pinfunction "5_5") (pintype "passive"))
      (node (ref "J2") (pin "75") (pinfunction "75_75") (pintype "passive"))
    )
    (net (code "76") (name "76") (class "Default")
      (node (ref "J1") (pin "76") (pinfunction "76_76") (pintype "passive"))
      (node (ref "J12") (pin "6") (pinfunction "6_6") (pintype "passive"))
      (node (ref "J2") (pin "76") (pinfunction "76_76") (pintype "passive"))
    )
    (net (code "77") (name "77") (class "Default")
      (node (ref "J1") (pin "77") (pinfunction "77_77") (pintype "passive"))
      (node (ref "J13") (pin "1") (pinfunction "1_1") (pintype "passive"))
      (node (ref "J2") (pin "77") (pinfunction "77_77") (pintype "passive"))
    )
    (net (code "78") (name "78") (class "Default")
      (node (ref "J1") (pin "78") (pinfunction "78_78") (pintype "passive"))
      (node (ref "J13") (pin "2") (pinfunction "2_2") (pintype "passive"))
      (node (ref "J2") (pin "78") (pinfunction "78_78") (pintype "passive"))
    )
    (net (code "79") (name "79") (class "Default")
      (node (ref "J1") (pin "79") (pinfunction "79_79") (pintype "passive"))
      (node (ref "J13") (pin "3") (pinfunction "3_3") (pintype "passive"))
      (node (ref "J2") (pin "79") (pinfunction "79_79") (pintype "passive"))
    )
    (net (code "80") (name "80") (class "Default")
      (node (ref "J1") (pin "80") (pinfunction "80_80") (pintype "passive"))
      (node (ref "J13") (pin "4") (pinfunction "4_4") (pintype "passive"))
      (node (ref "J2") (pin "80") (pinfunction "80_80") (pintype "passive"))
      (node (ref "TP7") (pin "1") (pinfunction "1_1") (pintype "power_in"))
    )
    (net (code "81") (name "81") (class "Default")
      (node (ref "J1") (pin "81") (pinfunction "81_81") (pintype "passive"))
      (node (ref "J13") (pin "5") (pinfunction "5_5") (pintype "passive"))
      (node (ref "J2") (pin "81") (pinfunction "81_81") (pintype "passive"))
    )
    (net (code "82") (name "82") (class "Default")
      (node (ref "J1") (pin "82") (pinfunction "82_82") (pintype "passive"))
      (node (ref "J13") (pin "6") (pinfunction "6_6") (pintype "passive"))
      (node (ref "J2") (pin "82") (pinfunction "82_82") (pintype "passive"))
      (node (ref "TP9") (pin "1") (pinfunction "1_1") (pintype "power_in"))
    )
    (net (code "83") (name "83") (class "Default")
      (node (ref "J1") (pin "83") (pinfunction "83_83") (pintype "passive"))
      (node (ref "J13") (pin "7") (pinfunction "7_7") (pintype "passive"))
      (node (ref "J2") (pin "83") (pinfunction "83_83") (pintype "passive"))
      (node (ref "R33") (pin "1") (pinfunction "1_1") (pintype "passive"))
    )
    (net (code "84") (name "84") (class "Default")
      (node (ref "J1") (pin "84") (pinfunction "84_84") (pintype "passive"))
      (node (ref "J13") (pin "8") (pinfunction "8_8") (pintype "passive"))
      (node (ref "J2") (pin "84") (pinfunction "84_84") (pintype "passive"))
      (node (ref "R34") (pin "1") (pinfunction "1_1") (pintype "passive"))
    )
    (net (code "85") (name "AGND") (class "Default")
      (node (ref "R33") (pin "2") (pinfunction "2_2") (pintype "passive"))
      (node (ref "R34") (pin "2") (pinfunction "2_2") (pintype "passive"))
      (node (ref "TP12") (pin "1") (pinfunction "1_1") (pintype "power_in"))
      (node (ref "TP14") (pin "1") (pinfunction "1_1") (pintype "power_in"))
    )
    (net (code "86") (name "DGND") (class "Default")
      (node (ref "R31") (pin "2") (pinfunction "2_2") (pintype "passive"))
      (node (ref "R32") (pin "2") (pinfunction "2_2") (pintype "passive"))
      (node (ref "TP11") (pin "1") (pinfunction "1_1") (pintype "power_in"))
      (node (ref "TP13") (pin "1") (pinfunction "1_1") (pintype "power_in"))
    )
  )
)
